# Supply.net
KiCad netlist of a schematic drawn in Altium Designer
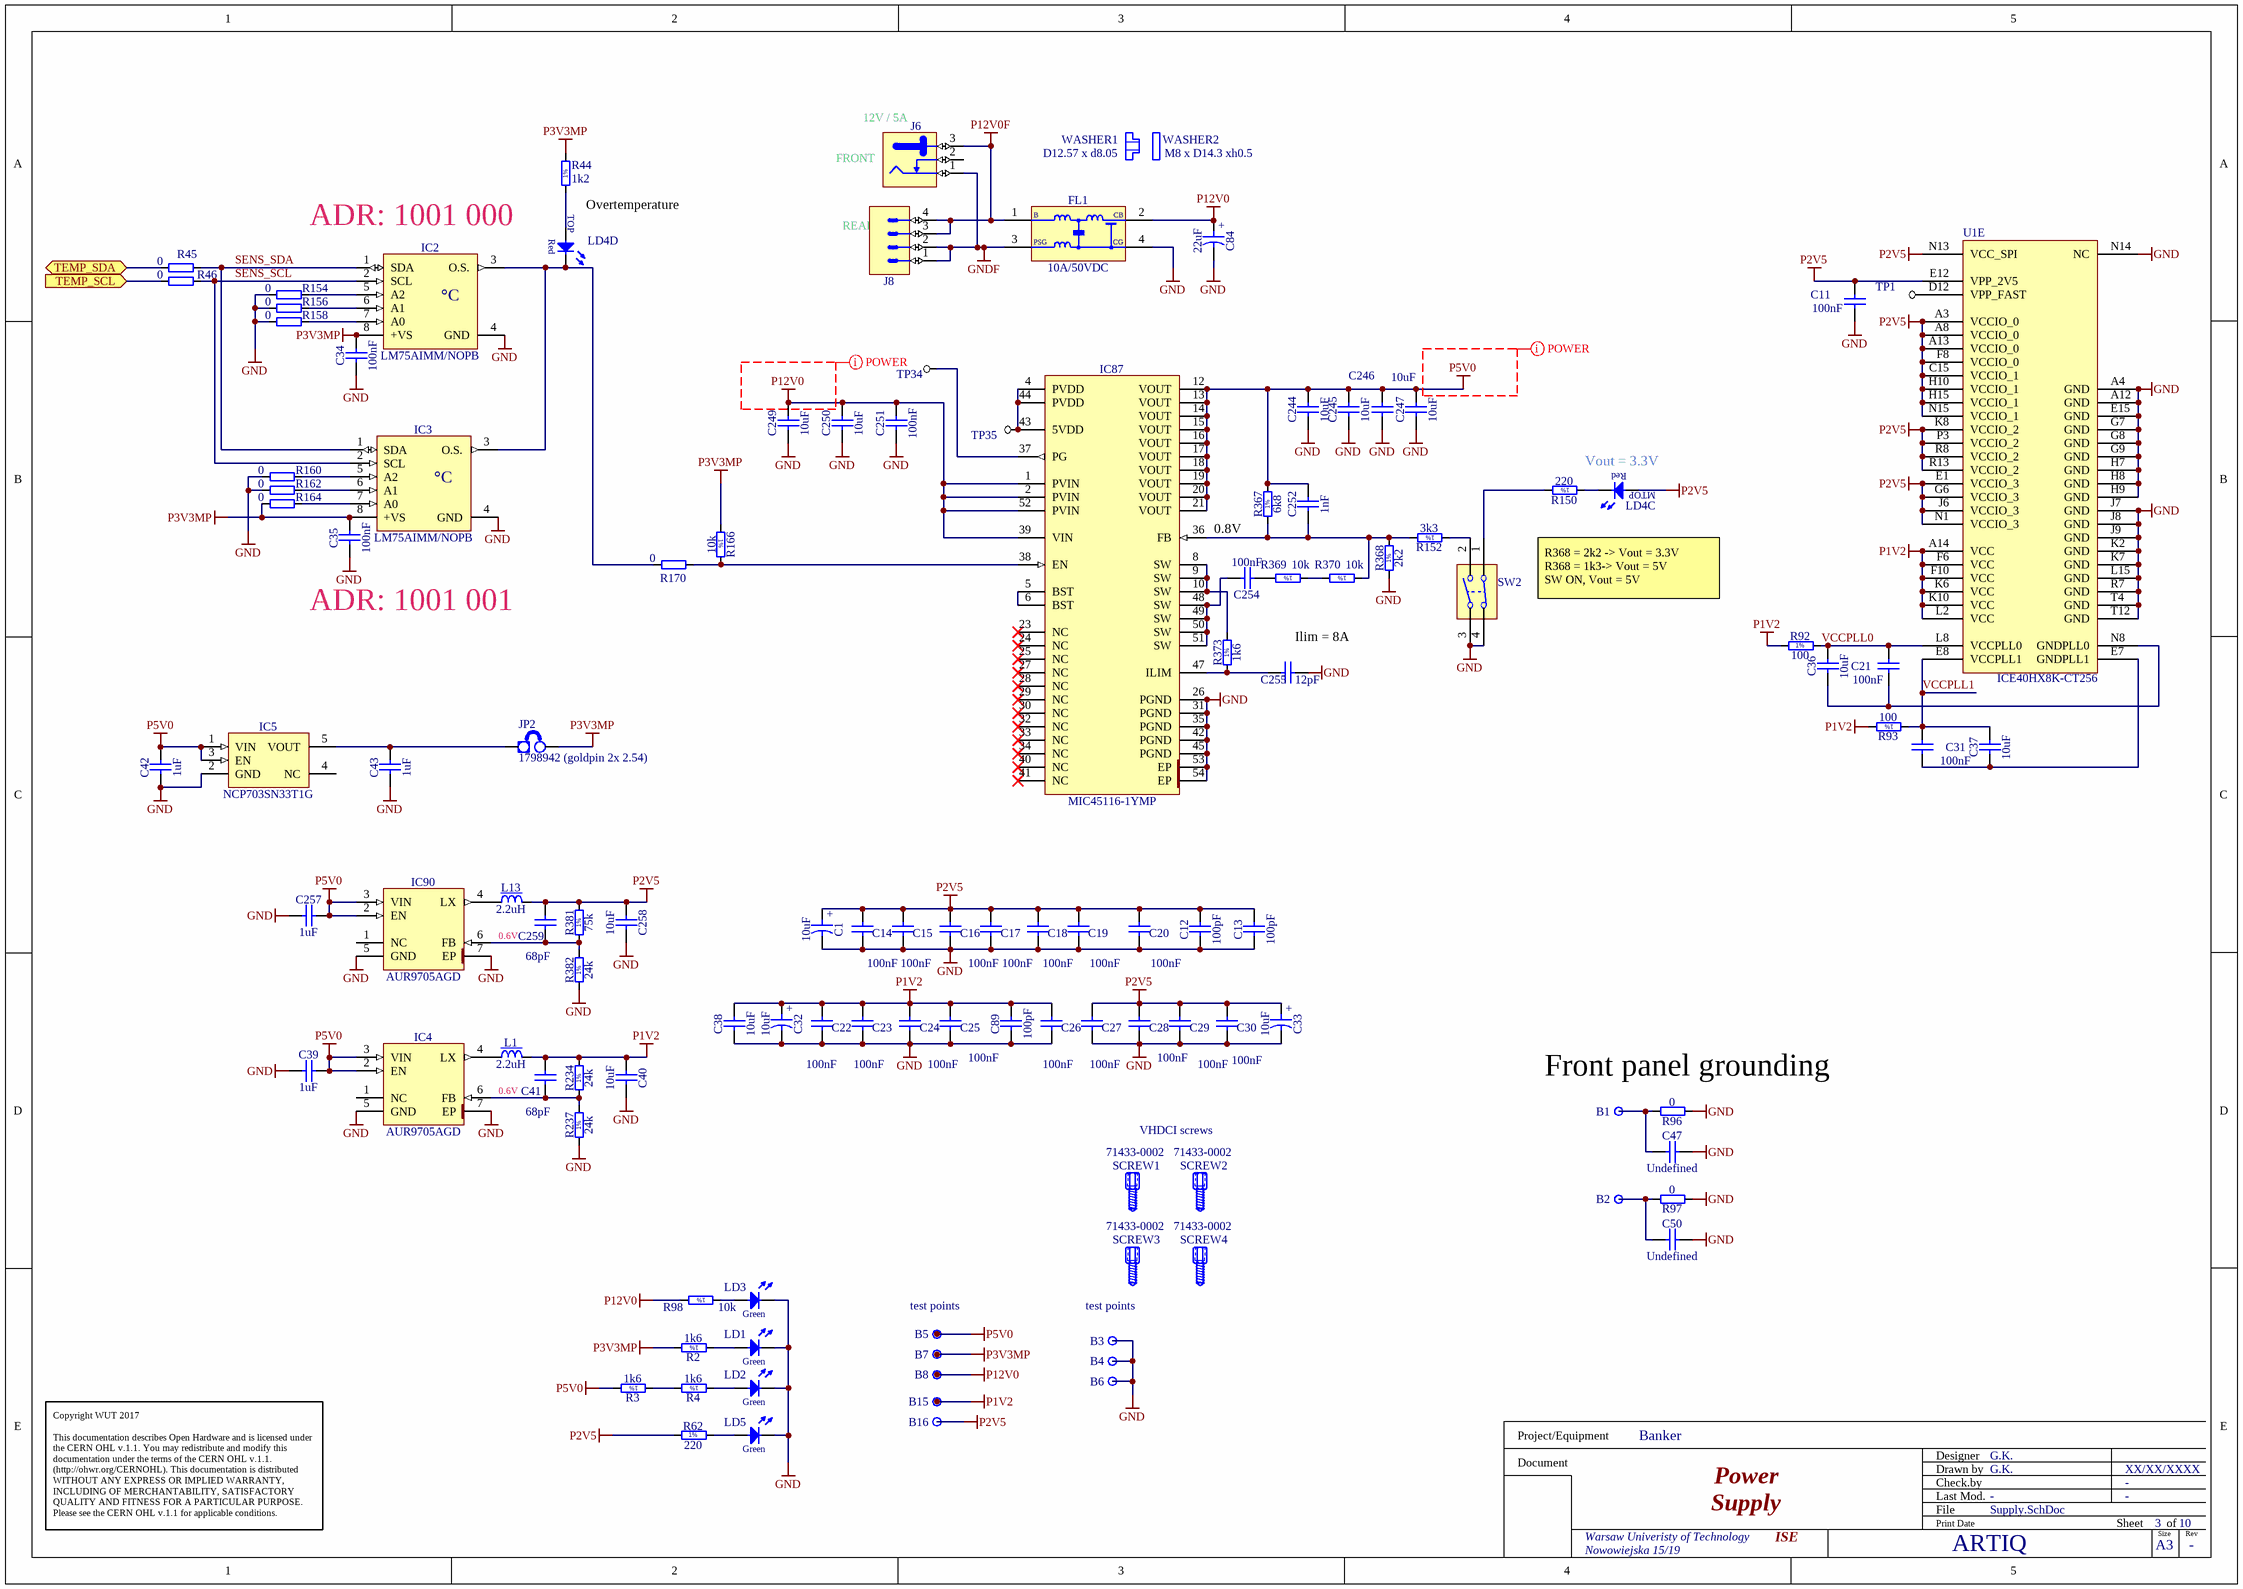
[diagram p0: Supply.SchDoc]

(export (version "E")
  (design (tool "Eeschema 10.0.6"))
  (components
    (comp (ref "B1")
      (value "Plated Hole")
      (footprint "MTG270_500")
      (description "Single Terminal Socket")
      (fields (field (name "PART NUMBER") "PLATED_HOLE2.7_PAD5.0") (field (name "AUTHOR") "CERN DEM JMW"))
      (libsource (lib "Eletro-mechanical") (part "Single Terminal Socket"))
    )
    (comp (ref "B2")
      (value "Plated Hole")
      (footprint "MTG270_500")
      (description "Single Terminal Socket")
      (fields (field (name "PART NUMBER") "PLATED_HOLE2.7_PAD5.0") (field (name "AUTHOR") "CERN DEM JMW"))
      (libsource (lib "Eletro-mechanical") (part "Single Terminal Socket"))
    )
    (comp (ref "B3")
      (value "Plated Hole")
      (footprint "c130h60")
      (description "Single Terminal Socket")
      (fields (field (name "PART NUMBER") "PLATED_HOLE0.6_PAD1.3") (field (name "AUTHOR") "CERN DEM MR"))
      (libsource (lib "Eletro-mechanical") (part "Single Terminal Socket"))
    )
    (comp (ref "B4")
      (value "Plated Hole")
      (footprint "c130h60")
      (description "Single Terminal Socket")
      (fields (field (name "PART NUMBER") "PLATED_HOLE0.6_PAD1.3") (field (name "AUTHOR") "CERN DEM MR"))
      (libsource (lib "Eletro-mechanical") (part "Single Terminal Socket"))
    )
    (comp (ref "B5")
      (value "Plated Hole")
      (footprint "c130h60")
      (description "Single Terminal Socket")
      (fields (field (name "PART NUMBER") "PLATED_HOLE0.6_PAD1.3") (field (name "AUTHOR") "CERN DEM MR"))
      (libsource (lib "Eletro-mechanical") (part "Single Terminal Socket"))
    )
    (comp (ref "B6")
      (value "Plated Hole")
      (footprint "c130h60")
      (description "Single Terminal Socket")
      (fields (field (name "PART NUMBER") "PLATED_HOLE0.6_PAD1.3") (field (name "AUTHOR") "CERN DEM MR"))
      (libsource (lib "Eletro-mechanical") (part "Single Terminal Socket"))
    )
    (comp (ref "B7")
      (value "Plated Hole")
      (footprint "c130h60")
      (description "Single Terminal Socket")
      (fields (field (name "PART NUMBER") "PLATED_HOLE0.6_PAD1.3") (field (name "AUTHOR") "CERN DEM MR"))
      (libsource (lib "Eletro-mechanical") (part "Single Terminal Socket"))
    )
    (comp (ref "B8")
      (value "Plated Hole")
      (footprint "c130h60")
      (description "Single Terminal Socket")
      (fields (field (name "PART NUMBER") "PLATED_HOLE0.6_PAD1.3") (field (name "AUTHOR") "CERN DEM MR"))
      (libsource (lib "Eletro-mechanical") (part "Single Terminal Socket"))
    )
    (comp (ref "B15")
      (value "Plated Hole")
      (footprint "c130h60")
      (description "Single Terminal Socket")
      (fields (field (name "PART NUMBER") "PLATED_HOLE0.6_PAD1.3") (field (name "AUTHOR") "CERN DEM MR"))
      (libsource (lib "Eletro-mechanical") (part "Single Terminal Socket"))
    )
    (comp (ref "B16")
      (value "Plated Hole")
      (footprint "c130h60")
      (description "Single Terminal Socket")
      (fields (field (name "PART NUMBER") "PLATED_HOLE0.6_PAD1.3") (field (name "AUTHOR") "CERN DEM MR"))
      (libsource (lib "Eletro-mechanical") (part "Single Terminal Socket"))
    )
    (comp (ref "C1")
      (value "10uF")
      (footprint "CAPAE430X540N")
      (description "Polarised capacitor")
      (fields
        (field (name "PART NUMBER") "CAE430-540_10UF_16V_20%")
        (field (name "VOLTAGE") "16V")
        (field (name "AUTHOR") "CERN DEM JLC")
      )
      (libsource (lib "Capacitors") (part "Capacitor - polarized"))
    )
    (comp (ref "C11")
      (value "100nF")
      (footprint "CAPC1005X55N")
      (description "Non-polarised capacitor")
      (fields
        (field (name "PART NUMBER") "CC0402_100NF_16V_10%_X5R")
        (field (name "VOLTAGE") "16V")
        (field (name "AUTHOR") "CERN DEM JLC")
      )
      (libsource (lib "Capacitors") (part "Capacitor - non polarized"))
    )
    (comp (ref "C12")
      (value "100pF")
      (footprint "CAPC1608X87N")
      (description "Non-polarised capacitor")
      (fields
        (field (name "PART NUMBER") "CC0603_100PF_50V_10%_X7R")
        (field (name "VOLTAGE") "50V")
        (field (name "AUTHOR") "CERN DEM JLC")
      )
      (libsource (lib "Capacitors") (part "Capacitor - non polarized"))
    )
    (comp (ref "C13")
      (value "100pF")
      (footprint "CAPC1608X87N")
      (description "Non-polarised capacitor")
      (fields
        (field (name "PART NUMBER") "CC0603_100PF_50V_10%_X7R")
        (field (name "VOLTAGE") "50V")
        (field (name "AUTHOR") "CERN DEM JLC")
      )
      (libsource (lib "Capacitors") (part "Capacitor - non polarized"))
    )
    (comp (ref "C14")
      (value "100nF")
      (footprint "CAPC1005X55N")
      (description "Non-polarised capacitor")
      (fields
        (field (name "PART NUMBER") "CC0402_100NF_16V_10%_X5R")
        (field (name "VOLTAGE") "16V")
        (field (name "AUTHOR") "CERN DEM JLC")
      )
      (libsource (lib "Capacitors") (part "Capacitor - non polarized"))
    )
    (comp (ref "C15")
      (value "100nF")
      (footprint "CAPC1005X55N")
      (description "Non-polarised capacitor")
      (fields
        (field (name "PART NUMBER") "CC0402_100NF_16V_10%_X5R")
        (field (name "VOLTAGE") "16V")
        (field (name "AUTHOR") "CERN DEM JLC")
      )
      (libsource (lib "Capacitors") (part "Capacitor - non polarized"))
    )
    (comp (ref "C16")
      (value "100nF")
      (footprint "CAPC1005X55N")
      (description "Non-polarised capacitor")
      (fields
        (field (name "PART NUMBER") "CC0402_100NF_16V_10%_X5R")
        (field (name "VOLTAGE") "16V")
        (field (name "AUTHOR") "CERN DEM JLC")
      )
      (libsource (lib "Capacitors") (part "Capacitor - non polarized"))
    )
    (comp (ref "C17")
      (value "100nF")
      (footprint "CAPC1005X55N")
      (description "Non-polarised capacitor")
      (fields
        (field (name "PART NUMBER") "CC0402_100NF_16V_10%_X5R")
        (field (name "VOLTAGE") "16V")
        (field (name "AUTHOR") "CERN DEM JLC")
      )
      (libsource (lib "Capacitors") (part "Capacitor - non polarized"))
    )
    (comp (ref "C18")
      (value "100nF")
      (footprint "CAPC1005X55N")
      (description "Non-polarised capacitor")
      (fields
        (field (name "PART NUMBER") "CC0402_100NF_16V_10%_X5R")
        (field (name "VOLTAGE") "16V")
        (field (name "AUTHOR") "CERN DEM JLC")
      )
      (libsource (lib "Capacitors") (part "Capacitor - non polarized"))
    )
    (comp (ref "C19")
      (value "100nF")
      (footprint "CAPC1005X55N")
      (description "Non-polarised capacitor")
      (fields
        (field (name "PART NUMBER") "CC0402_100NF_16V_10%_X5R")
        (field (name "VOLTAGE") "16V")
        (field (name "AUTHOR") "CERN DEM JLC")
      )
      (libsource (lib "Capacitors") (part "Capacitor - non polarized"))
    )
    (comp (ref "C20")
      (value "100nF")
      (footprint "CAPC1005X55N")
      (description "Non-polarised capacitor")
      (fields
        (field (name "PART NUMBER") "CC0402_100NF_16V_10%_X5R")
        (field (name "VOLTAGE") "16V")
        (field (name "AUTHOR") "CERN DEM JLC")
      )
      (libsource (lib "Capacitors") (part "Capacitor - non polarized"))
    )
    (comp (ref "C21")
      (value "100nF")
      (footprint "CAPC1005X55N")
      (description "Non-polarised capacitor")
      (fields
        (field (name "PART NUMBER") "CC0402_100NF_16V_10%_X5R")
        (field (name "VOLTAGE") "16V")
        (field (name "AUTHOR") "CERN DEM JLC")
      )
      (libsource (lib "Capacitors") (part "Capacitor - non polarized"))
    )
    (comp (ref "C22")
      (value "100nF")
      (footprint "CAPC1005X55N")
      (description "Non-polarised capacitor")
      (fields
        (field (name "PART NUMBER") "CC0402_100NF_16V_10%_X5R")
        (field (name "VOLTAGE") "16V")
        (field (name "AUTHOR") "CERN DEM JLC")
      )
      (libsource (lib "Capacitors") (part "Capacitor - non polarized"))
    )
    (comp (ref "C23")
      (value "100nF")
      (footprint "CAPC1005X55N")
      (description "Non-polarised capacitor")
      (fields
        (field (name "PART NUMBER") "CC0402_100NF_16V_10%_X5R")
        (field (name "VOLTAGE") "16V")
        (field (name "AUTHOR") "CERN DEM JLC")
      )
      (libsource (lib "Capacitors") (part "Capacitor - non polarized"))
    )
    (comp (ref "C24")
      (value "100nF")
      (footprint "CAPC1005X55N")
      (description "Non-polarised capacitor")
      (fields
        (field (name "PART NUMBER") "CC0402_100NF_16V_10%_X5R")
        (field (name "VOLTAGE") "16V")
        (field (name "AUTHOR") "CERN DEM JLC")
      )
      (libsource (lib "Capacitors") (part "Capacitor - non polarized"))
    )
    (comp (ref "C25")
      (value "100nF")
      (footprint "CAPC1005X55N")
      (description "Non-polarised capacitor")
      (fields
        (field (name "PART NUMBER") "CC0402_100NF_16V_10%_X5R")
        (field (name "VOLTAGE") "16V")
        (field (name "AUTHOR") "CERN DEM JLC")
      )
      (libsource (lib "Capacitors") (part "Capacitor - non polarized"))
    )
    (comp (ref "C26")
      (value "100nF")
      (footprint "CAPC1005X55N")
      (description "Non-polarised capacitor")
      (fields
        (field (name "PART NUMBER") "CC0402_100NF_16V_10%_X5R")
        (field (name "VOLTAGE") "16V")
        (field (name "AUTHOR") "CERN DEM JLC")
      )
      (libsource (lib "Capacitors") (part "Capacitor - non polarized"))
    )
    (comp (ref "C27")
      (value "100nF")
      (footprint "CAPC1005X55N")
      (description "Non-polarised capacitor")
      (fields
        (field (name "PART NUMBER") "CC0402_100NF_16V_10%_X5R")
        (field (name "VOLTAGE") "16V")
        (field (name "AUTHOR") "CERN DEM JLC")
      )
      (libsource (lib "Capacitors") (part "Capacitor - non polarized"))
    )
    (comp (ref "C28")
      (value "100nF")
      (footprint "CAPC1005X55N")
      (description "Non-polarised capacitor")
      (fields
        (field (name "PART NUMBER") "CC0402_100NF_16V_10%_X5R")
        (field (name "VOLTAGE") "16V")
        (field (name "AUTHOR") "CERN DEM JLC")
      )
      (libsource (lib "Capacitors") (part "Capacitor - non polarized"))
    )
    (comp (ref "C29")
      (value "100nF")
      (footprint "CAPC1005X55N")
      (description "Non-polarised capacitor")
      (fields
        (field (name "PART NUMBER") "CC0402_100NF_16V_10%_X5R")
        (field (name "VOLTAGE") "16V")
        (field (name "AUTHOR") "CERN DEM JLC")
      )
      (libsource (lib "Capacitors") (part "Capacitor - non polarized"))
    )
    (comp (ref "C30")
      (value "100nF")
      (footprint "CAPC1005X55N")
      (description "Non-polarised capacitor")
      (fields
        (field (name "PART NUMBER") "CC0402_100NF_16V_10%_X5R")
        (field (name "VOLTAGE") "16V")
        (field (name "AUTHOR") "CERN DEM JLC")
      )
      (libsource (lib "Capacitors") (part "Capacitor - non polarized"))
    )
    (comp (ref "C31")
      (value "100nF")
      (footprint "CAPC1005X55N")
      (description "Non-polarised capacitor")
      (fields
        (field (name "PART NUMBER") "CC0402_100NF_16V_10%_X5R")
        (field (name "VOLTAGE") "16V")
        (field (name "AUTHOR") "CERN DEM JLC")
      )
      (libsource (lib "Capacitors") (part "Capacitor - non polarized"))
    )
    (comp (ref "C32")
      (value "10uF")
      (footprint "CAPAE430X540N")
      (description "Polarised capacitor")
      (fields
        (field (name "PART NUMBER") "CAE430-540_10UF_16V_20%")
        (field (name "VOLTAGE") "16V")
        (field (name "AUTHOR") "CERN DEM JLC")
      )
      (libsource (lib "Capacitors") (part "Capacitor - polarized"))
    )
    (comp (ref "C33")
      (value "10uF")
      (footprint "CAPAE430X540N")
      (description "Polarised capacitor")
      (fields
        (field (name "PART NUMBER") "CAE430-540_10UF_16V_20%")
        (field (name "VOLTAGE") "16V")
        (field (name "AUTHOR") "CERN DEM JLC")
      )
      (libsource (lib "Capacitors") (part "Capacitor - polarized"))
    )
    (comp (ref "C34")
      (value "100nF")
      (footprint "CAPC1005X55N")
      (description "Non-polarised capacitor")
      (fields
        (field (name "PART NUMBER") "CC0402_100NF_16V_10%_X5R")
        (field (name "VOLTAGE") "16V")
        (field (name "AUTHOR") "CERN DEM JLC")
      )
      (libsource (lib "Capacitors") (part "Capacitor - non polarized"))
    )
    (comp (ref "C35")
      (value "100nF")
      (footprint "CAPC1005X55N")
      (description "Non-polarised capacitor")
      (fields
        (field (name "PART NUMBER") "CC0402_100NF_16V_10%_X5R")
        (field (name "VOLTAGE") "16V")
        (field (name "AUTHOR") "CERN DEM JLC")
      )
      (libsource (lib "Capacitors") (part "Capacitor - non polarized"))
    )
    (comp (ref "C36")
      (value "10uF")
      (footprint "CAPC1005X70N")
      (description "Non-polarised capacitor")
      (fields
        (field (name "PART NUMBER") "CC0402_10UF_6.3V_20%_X5R")
        (field (name "VOLTAGE") "6.3V")
        (field (name "AUTHOR") "CERN DEM JLC")
      )
      (libsource (lib "Capacitors") (part "Capacitor - non polarized"))
    )
    (comp (ref "C37")
      (value "10uF")
      (footprint "CAPC1005X70N")
      (description "Non-polarised capacitor")
      (fields
        (field (name "PART NUMBER") "CC0402_10UF_6.3V_20%_X5R")
        (field (name "VOLTAGE") "6.3V")
        (field (name "AUTHOR") "CERN DEM JLC")
      )
      (libsource (lib "Capacitors") (part "Capacitor - non polarized"))
    )
    (comp (ref "C38")
      (value "10uF")
      (footprint "CAPC2012X135N")
      (description "Non-polarised capacitor")
      (fields
        (field (name "PART NUMBER") "CC0805_10UF_16V_10%_X5R")
        (field (name "VOLTAGE") "16V")
        (field (name "AUTHOR") "CERN DEM JLC")
      )
      (libsource (lib "Capacitors") (part "Capacitor - non polarized"))
    )
    (comp (ref "C39")
      (value "1uF")
      (footprint "CAPC1005X55N")
      (description "Non-polarised capacitor")
      (fields
        (field (name "PART NUMBER") "CC0402_1UF_16V_10%_X5R")
        (field (name "VOLTAGE") "16V")
        (field (name "AUTHOR") "CERN DEM JLC")
      )
      (libsource (lib "Capacitors") (part "Capacitor - non polarized"))
    )
    (comp (ref "C40")
      (value "10uF")
      (footprint "CAPC2012X135N")
      (description "Non-polarised capacitor")
      (fields
        (field (name "PART NUMBER") "CC0805_10UF_16V_10%_X5R")
        (field (name "VOLTAGE") "16V")
        (field (name "AUTHOR") "CERN DEM JLC")
      )
      (libsource (lib "Capacitors") (part "Capacitor - non polarized"))
    )
    (comp (ref "C41")
      (value "68pF")
      (footprint "CAPC1608X87N")
      (description "Non-polarised capacitor")
      (fields
        (field (name "PART NUMBER") "CC0603_68PF_50V_5%_NP0")
        (field (name "VOLTAGE") "50V")
        (field (name "AUTHOR") "CERN DEM JLC")
      )
      (libsource (lib "Capacitors") (part "Capacitor - non polarized"))
    )
    (comp (ref "C42")
      (value "1uF")
      (footprint "CAPC2012X140N")
      (description "Non-polarised capacitor")
      (fields
        (field (name "PART NUMBER") "CC0805_1UF_35V_20%_X7R")
        (field (name "VOLTAGE") "35V")
        (field (name "AUTHOR") "CERN DEM JLC")
      )
      (libsource (lib "Capacitors") (part "Capacitor - non polarized"))
    )
    (comp (ref "C43")
      (value "1uF")
      (footprint "CAPC2012X140N")
      (description "Non-polarised capacitor")
      (fields
        (field (name "PART NUMBER") "CC0805_1UF_35V_20%_X7R")
        (field (name "VOLTAGE") "35V")
        (field (name "AUTHOR") "CERN DEM JLC")
      )
      (libsource (lib "Capacitors") (part "Capacitor - non polarized"))
    )
    (comp (ref "C47")
      (value "Undefined")
      (footprint "CAPC2012X135N")
      (description "Non-polarised capacitor")
      (fields (field (name "PART NUMBER") "CC0805_NO-VALUE") (field (name "AUTHOR") "CERN DEM JLC"))
      (libsource (lib "Capacitors") (part "Capacitor - non polarized"))
    )
    (comp (ref "C50")
      (value "Undefined")
      (footprint "CAPC2012X135N")
      (description "Non-polarised capacitor")
      (fields (field (name "PART NUMBER") "CC0805_NO-VALUE") (field (name "AUTHOR") "CERN DEM JLC"))
      (libsource (lib "Capacitors") (part "Capacitor - non polarized"))
    )
    (comp (ref "C84")
      (value "22uF")
      (footprint "CAPAE530X540N")
      (description "Polarised capacitor")
      (fields
        (field (name "PART NUMBER") "CAE530-540_22UF_16V_20%")
        (field (name "VOLTAGE") "16V")
        (field (name "AUTHOR") "CERN DEM JLC")
      )
      (libsource (lib "Capacitors") (part "Capacitor - polarized"))
    )
    (comp (ref "C89")
      (value "100pF")
      (footprint "CAPC1608X87N")
      (description "Non-polarised capacitor")
      (fields
        (field (name "PART NUMBER") "CC0603_100PF_50V_10%_X7R")
        (field (name "VOLTAGE") "50V")
        (field (name "AUTHOR") "CERN DEM JLC")
      )
      (libsource (lib "Capacitors") (part "Capacitor - non polarized"))
    )
    (comp (ref "C244")
      (value "10uF")
      (footprint "CAPC2012X135N")
      (description "Non-polarised capacitor")
      (fields
        (field (name "PART NUMBER") "CC0805_10UF_16V_10%_X5R")
        (field (name "VOLTAGE") "16V")
        (field (name "AUTHOR") "CERN DEM JLC")
      )
      (libsource (lib "Capacitors") (part "Capacitor - non polarized"))
    )
    (comp (ref "C245")
      (value "10uF")
      (footprint "CAPC2012X135N")
      (description "Non-polarised capacitor")
      (fields
        (field (name "PART NUMBER") "CC0805_10UF_16V_10%_X5R")
        (field (name "VOLTAGE") "16V")
        (field (name "AUTHOR") "CERN DEM JLC")
      )
      (libsource (lib "Capacitors") (part "Capacitor - non polarized"))
    )
    (comp (ref "C246")
      (value "10uF")
      (footprint "CAPC2012X135N")
      (description "Non-polarised capacitor")
      (fields
        (field (name "PART NUMBER") "CC0805_10UF_16V_10%_X5R")
        (field (name "VOLTAGE") "16V")
        (field (name "AUTHOR") "CERN DEM JLC")
      )
      (libsource (lib "Capacitors") (part "Capacitor - non polarized"))
    )
    (comp (ref "C247")
      (value "10uF")
      (footprint "CAPC2012X135N")
      (description "Non-polarised capacitor")
      (fields
        (field (name "PART NUMBER") "CC0805_10UF_16V_10%_X5R")
        (field (name "VOLTAGE") "16V")
        (field (name "AUTHOR") "CERN DEM JLC")
      )
      (libsource (lib "Capacitors") (part "Capacitor - non polarized"))
    )
    (comp (ref "C249")
      (value "10uF")
      (footprint "CAPC2012X135N")
      (description "Non-polarised capacitor")
      (fields
        (field (name "PART NUMBER") "CC0805_10UF_16V_10%_X5R")
        (field (name "VOLTAGE") "16V")
        (field (name "AUTHOR") "CERN DEM JLC")
      )
      (libsource (lib "Capacitors") (part "Capacitor - non polarized"))
    )
    (comp (ref "C250")
      (value "10uF")
      (footprint "CAPC2012X135N")
      (description "Non-polarised capacitor")
      (fields
        (field (name "PART NUMBER") "CC0805_10UF_16V_10%_X5R")
        (field (name "VOLTAGE") "16V")
        (field (name "AUTHOR") "CERN DEM JLC")
      )
      (libsource (lib "Capacitors") (part "Capacitor - non polarized"))
    )
    (comp (ref "C251")
      (value "100nF")
      (footprint "CAPC1005X55N")
      (description "Non-polarised capacitor")
      (fields
        (field (name "PART NUMBER") "CC0402_100NF_16V_10%_X5R")
        (field (name "VOLTAGE") "16V")
        (field (name "AUTHOR") "CERN DEM JLC")
      )
      (libsource (lib "Capacitors") (part "Capacitor - non polarized"))
    )
    (comp (ref "C252")
      (value "1nF")
      (footprint "CAPC1608X87N")
      (description "Non-polarised capacitor")
      (fields
        (field (name "PART NUMBER") "CC0603_1NF_100V_10%_X7R")
        (field (name "VOLTAGE") "100V")
        (field (name "AUTHOR") "CERN DEM JLC")
      )
      (libsource (lib "Capacitors") (part "Capacitor - non polarized"))
    )
    (comp (ref "C254")
      (value "100nF")
      (footprint "CAPC1005X55N")
      (description "Non-polarised capacitor")
      (fields
        (field (name "PART NUMBER") "CC0402_100NF_16V_10%_X5R")
        (field (name "VOLTAGE") "16V")
        (field (name "AUTHOR") "CERN DEM JLC")
      )
      (libsource (lib "Capacitors") (part "Capacitor - non polarized"))
    )
    (comp (ref "C255")
      (value "12pF")
      (footprint "CAPC1005X55N")
      (description "Non-polarised capacitor")
      (fields
        (field (name "PART NUMBER") "CC0402_12PF_50V_5%_C0G")
        (field (name "VOLTAGE") "50V")
        (field (name "AUTHOR") "CERN DEM JLC")
      )
      (libsource (lib "Capacitors") (part "Capacitor - non polarized"))
    )
    (comp (ref "C257")
      (value "1uF")
      (footprint "CAPC1005X55N")
      (description "Non-polarised capacitor")
      (fields
        (field (name "PART NUMBER") "CC0402_1UF_16V_10%_X5R")
        (field (name "VOLTAGE") "16V")
        (field (name "AUTHOR") "CERN DEM JLC")
      )
      (libsource (lib "Capacitors") (part "Capacitor - non polarized"))
    )
    (comp (ref "C258")
      (value "10uF")
      (footprint "CAPC2012X135N")
      (description "Non-polarised capacitor")
      (fields
        (field (name "PART NUMBER") "CC0805_10UF_16V_10%_X5R")
        (field (name "VOLTAGE") "16V")
        (field (name "AUTHOR") "CERN DEM JLC")
      )
      (libsource (lib "Capacitors") (part "Capacitor - non polarized"))
    )
    (comp (ref "C259")
      (value "68pF")
      (footprint "CAPC1608X87N")
      (description "Non-polarised capacitor")
      (fields
        (field (name "PART NUMBER") "CC0603_68PF_50V_5%_NP0")
        (field (name "VOLTAGE") "50V")
        (field (name "AUTHOR") "CERN DEM JLC")
      )
      (libsource (lib "Capacitors") (part "Capacitor - non polarized"))
    )
    (comp (ref "FL1")
      (value "10A/50VDC")
      (footprint "FIL_MURATA_BNX02")
      (description "Block Type EMIFIL (LC Combined)")
      (fields
        (field (name "PART NUMBER") "FIL_MURATA_BNX022-01L")
        (field (name "MANUFACTURER") "MURATA")
        (field (name "AUTHOR") "CERN DEM JLC")
      )
      (libsource (lib "Inductors & Transformers") (part "FIL_MURATA_BNX02"))
    )
    (comp (ref "IC2")
      (value "LM75AIMM/NOPB")
      (footprint "SOP65P490X109-8N")
      (description "Digital Temperature Sensor and Thermal Watchdog with Two-Wire Interface")
      (fields (field (name "MANUFACTURER") "TEXAS INSTRUMENTS") (field (name "AUTHOR") "CERN DEM JLC"))
      (libsource (lib "ICs And Semiconductors") (part "LM75"))
    )
    (comp (ref "IC3")
      (value "LM75AIMM/NOPB")
      (footprint "SOP65P490X109-8N")
      (description "Digital Temperature Sensor and Thermal Watchdog with Two-Wire Interface")
      (fields (field (name "MANUFACTURER") "TEXAS INSTRUMENTS") (field (name "AUTHOR") "CERN DEM JLC"))
      (libsource (lib "ICs And Semiconductors") (part "LM75"))
    )
    (comp (ref "IC4")
      (value "AUR9705AGD")
      (footprint "SON65P200X200X80-7N-R65X145")
      (description "0V to 6V Input, 1A, 1.5MHz, Step-Down DC-DC Converter")
      (fields (field (name "MANUFACTURER") "DIODES INCORPORATED") (field (name "AUTHOR") "CERN DEM MR"))
      (libsource (lib "ICs And Semiconductors") (part "AUR9705AGD"))
    )
    (comp (ref "IC5")
      (value "NCP703SN33T1G")
      (footprint "SOT95P275X110-5N")
      (description "3.3V 300mA, Ultra-Low Quiescent Current, IQ 12uA, Ultra-Low Noise, LDO Voltage Regulator")
      (fields (field (name "MANUFACTURER") "ON SEMICONDUCTOR") (field (name "AUTHOR") "CERN DEM JLC"))
      (libsource (lib "ICs And Semiconductors") (part "NCP703SN"))
    )
    (comp (ref "IC87")
      (value "MIC45116-1YMP")
      (footprint "MICROCHIP_H3QFN88-52LD-PL-3")
      (description "0.8V to 85% PVIN (4.75-19V), 6A Synchronous Step-Down Regulator Module")
      (fields (field (name "MANUFACTURER") "MICROCHIP TECHNOLOGY") (field (name "AUTHOR") "CERN DEM JMW"))
      (libsource (lib "ICs And Semiconductors") (part "MIC45116"))
    )
    (comp (ref "IC90")
      (value "AUR9705AGD")
      (footprint "SON65P200X200X80-7N-R65X145")
      (description "0V to 6V Input, 1A, 1.5MHz, Step-Down DC-DC Converter")
      (fields (field (name "MANUFACTURER") "DIODES INCORPORATED") (field (name "AUTHOR") "CERN DEM MR"))
      (libsource (lib "ICs And Semiconductors") (part "AUR9705AGD"))
    )
    (comp (ref "J6")
      (value "Jack")
      (footprint "SWITCHCRAFT_L712RA")
      (description "24V /3. 5A, 2.1mm Diameter Pin, SMD DC Power Supply Connector With  Break Contact")
      (fields
        (field (name "PART NUMBER") "SWITCHCRAFT_L712RA")
        (field (name "MANUFACTURER") "SWITCHCRAFT")
        (field (name "AUTHOR") "GK")
      )
      (libsource (lib "LIBRARY_SCH") (part "CON_DC_5A_THT_RA"))
    )
    (comp (ref "J8")
      (value "Mini-Fit Jr.™")
      (footprint "MOLEX_39-30-0040")
      (description "Connector 4 Male")
      (fields
        (field (name "PART NUMBER") "MOLEX_39-30-0040")
        (field (name "MANUFACTURER") "MOLEX")
        (field (name "AUTHOR") "CERN DEM JLC")
      )
      (libsource (lib "Connectors") (part "Connector 4 Male"))
    )
    (comp (ref "JP2")
      (value "1798942 (goldpin 2x 2.54)")
      (footprint "jump")
      (description "Jumper")
      (libsource (lib "LIBRARY_SCH") (part "JUMPER"))
    )
    (comp (ref "L1")
      (value "2.2uH")
      (footprint "IND_MURATA_LQH44PN_P0")
      (description "Inductor With Core")
      (fields
        (field (name "PART NUMBER") "IND_2.2UH_20%_MURATA_LQH44PN2R2MP0L")
        (field (name "POWER") "1.8A")
        (field (name "AUTHOR") "CERN DEM JLC")
      )
      (libsource (lib "Inductors & Transformers") (part "Inductor With Magnetic core"))
    )
    (comp (ref "L13")
      (value "2.2uH")
      (footprint "IND_MURATA_LQH44PN_P0")
      (description "Inductor With Core")
      (fields
        (field (name "PART NUMBER") "IND_2.2UH_20%_MURATA_LQH44PN2R2MP0L")
        (field (name "POWER") "1.8A")
        (field (name "AUTHOR") "CERN DEM JLC")
      )
      (libsource (lib "Inductors & Transformers") (part "Inductor With Magnetic core"))
    )
    (comp (ref "LD1")
      (value "Green")
      (footprint "LED_KINGBRIGHT_KPH-1608CGCK")
      (description "LED Green 1C 2A")
      (fields
        (field (name "PART NUMBER") "LED_KINGBRIGHT_KPH-1608CGCK")
        (field (name "MANUFACTURER") "KINGBRIGHT")
        (field (name "AUTHOR") "CERN DEM JLC")
      )
      (libsource (lib "ICs And Semiconductors") (part "LED Green 1C 2A"))
    )
    (comp (ref "LD2")
      (value "Green")
      (footprint "LED_KINGBRIGHT_KPH-1608CGCK")
      (description "LED Green 1C 2A")
      (fields
        (field (name "PART NUMBER") "LED_KINGBRIGHT_KPH-1608CGCK")
        (field (name "MANUFACTURER") "KINGBRIGHT")
        (field (name "AUTHOR") "CERN DEM JLC")
      )
      (libsource (lib "ICs And Semiconductors") (part "LED Green 1C 2A"))
    )
    (comp (ref "LD3")
      (value "Green")
      (footprint "LED_KINGBRIGHT_KPH-1608CGCK")
      (description "LED Green 1C 2A")
      (fields
        (field (name "PART NUMBER") "LED_KINGBRIGHT_KPH-1608CGCK")
        (field (name "MANUFACTURER") "KINGBRIGHT")
        (field (name "AUTHOR") "CERN DEM JLC")
      )
      (libsource (lib "ICs And Semiconductors") (part "LED Green 1C 2A"))
    )
    (comp (ref "LD4")
      (value "Green/Green/HeRed/HeRed")
      (footprint "LED_BIVAR_H485CHHGGDL")
      (description "LED x4 G-1C2A-BOT_G-3C4A_H-5C6A_H-7C8A-TOP")
      (fields
        (field (name "PART NUMBER") "LED_BIVAR_H485CHHGGDL")
        (field (name "MANUFACTURER") "BIVAR")
        (field (name "AUTHOR") "CERN DEM BC")
      )
      (libsource (lib "ICs And Semiconductors") (part "LED x4 G-1C2A-BOT_G-3C4A_H-5C6A_H-7C8A-TOP"))
    )
    (comp (ref "LD5")
      (value "Green")
      (footprint "LED_KINGBRIGHT_KPH-1608CGCK")
      (description "LED Green 1C 2A")
      (fields
        (field (name "PART NUMBER") "LED_KINGBRIGHT_KPH-1608CGCK")
        (field (name "MANUFACTURER") "KINGBRIGHT")
        (field (name "AUTHOR") "CERN DEM JLC")
      )
      (libsource (lib "ICs And Semiconductors") (part "LED Green 1C 2A"))
    )
    (comp (ref "R2")
      (value "1k6")
      (footprint "RESC1005X40N")
      (description "Resistor - 1%")
      (fields
        (field (name "PART NUMBER") "R0402_1K6_1%_0.0625W_100PPM")
        (field (name "POWER") "0.0625W")
        (field (name "AUTHOR") "CERN DEM JLC")
      )
      (libsource (lib "Resistors") (part "Resistor - 1%"))
    )
    (comp (ref "R3")
      (value "1k6")
      (footprint "RESC1005X40N")
      (description "Resistor - 1%")
      (fields
        (field (name "PART NUMBER") "R0402_1K6_1%_0.0625W_100PPM")
        (field (name "POWER") "0.0625W")
        (field (name "AUTHOR") "CERN DEM JLC")
      )
      (libsource (lib "Resistors") (part "Resistor - 1%"))
    )
    (comp (ref "R4")
      (value "1k6")
      (footprint "RESC1005X40N")
      (description "Resistor - 1%")
      (fields
        (field (name "PART NUMBER") "R0402_1K6_1%_0.0625W_100PPM")
        (field (name "POWER") "0.0625W")
        (field (name "AUTHOR") "CERN DEM JLC")
      )
      (libsource (lib "Resistors") (part "Resistor - 1%"))
    )
    (comp (ref "R44")
      (value "1k2")
      (footprint "RESC1608X55N")
      (description "Resistor - 1%")
      (fields
        (field (name "PART NUMBER") "R0603_1K2_1%_0.1W_100PPM")
        (field (name "POWER") "0.1W")
        (field (name "AUTHOR") "CERN DEM JLC")
      )
      (libsource (lib "Resistors") (part "Resistor - 1%"))
    )
    (comp (ref "R45")
      (value "0")
      (footprint "RESC1005X40N")
      (description "Resistor")
      (fields
        (field (name "PART NUMBER") "R0402_0R_JUMPER")
        (field (name "MANUFACTURER") "GENERIC")
        (field (name "AUTHOR") "CERN DEM JLC")
      )
      (libsource (lib "Resistors") (part "Resistor"))
    )
    (comp (ref "R46")
      (value "0")
      (footprint "RESC1005X40N")
      (description "Resistor")
      (fields
        (field (name "PART NUMBER") "R0402_0R_JUMPER")
        (field (name "MANUFACTURER") "GENERIC")
        (field (name "AUTHOR") "CERN DEM JLC")
      )
      (libsource (lib "Resistors") (part "Resistor"))
    )
    (comp (ref "R62")
      (value "220")
      (footprint "RESC1608X55N")
      (description "Resistor - 1%")
      (fields
        (field (name "PART NUMBER") "R0603_220R_1%_0.1W_100PPM")
        (field (name "POWER") "0.1W")
        (field (name "AUTHOR") "CERN DEM JLC")
      )
      (libsource (lib "Resistors") (part "Resistor - 1%"))
    )
    (comp (ref "R92")
      (value "100")
      (footprint "RESC1005X40N")
      (description "Resistor - 1%")
      (fields
        (field (name "PART NUMBER") "R0402_100R_1%_0.0625W_100PPM")
        (field (name "POWER") "0.0625W")
        (field (name "AUTHOR") "CERN DEM JLC")
      )
      (libsource (lib "Resistors") (part "Resistor - 1%"))
    )
    (comp (ref "R93")
      (value "100")
      (footprint "RESC1005X40N")
      (description "Resistor - 1%")
      (fields
        (field (name "PART NUMBER") "R0402_100R_1%_0.0625W_100PPM")
        (field (name "POWER") "0.0625W")
        (field (name "AUTHOR") "CERN DEM JLC")
      )
      (libsource (lib "Resistors") (part "Resistor - 1%"))
    )
    (comp (ref "R96")
      (value "0")
      (footprint "RESC1608X55N")
      (description "Resistor")
      (fields
        (field (name "PART NUMBER") "R0603_0R_JUMPER")
        (field (name "MANUFACTURER") "GENERIC")
        (field (name "AUTHOR") "CERN DEM JLC")
      )
      (libsource (lib "Resistors") (part "Resistor"))
    )
    (comp (ref "R97")
      (value "0")
      (footprint "RESC1608X55N")
      (description "Resistor")
      (fields
        (field (name "PART NUMBER") "R0603_0R_JUMPER")
        (field (name "MANUFACTURER") "GENERIC")
        (field (name "AUTHOR") "CERN DEM JLC")
      )
      (libsource (lib "Resistors") (part "Resistor"))
    )
    (comp (ref "R98")
      (value "10k")
      (footprint "RESC1005X40N")
      (description "Resistor - 1%")
      (fields
        (field (name "PART NUMBER") "R0402_10K_1%_0.0625W_100PPM")
        (field (name "POWER") "0.0625W")
        (field (name "AUTHOR") "CERN DEM JLC")
      )
      (libsource (lib "Resistors") (part "Resistor - 1%"))
    )
    (comp (ref "R150")
      (value "220")
      (footprint "RESC1608X55N")
      (description "Resistor - 1%")
      (fields
        (field (name "PART NUMBER") "R0603_220R_1%_0.1W_100PPM")
        (field (name "POWER") "0.1W")
        (field (name "AUTHOR") "CERN DEM JLC")
      )
      (libsource (lib "Resistors") (part "Resistor - 1%"))
    )
    (comp (ref "R152")
      (value "3k3")
      (footprint "RESC1005X40N")
      (description "Resistor - 1%")
      (fields
        (field (name "PART NUMBER") "R0402_3K3_1%_0.0625W_100PPM")
        (field (name "POWER") "0.0625W")
        (field (name "AUTHOR") "CERN DEM JLC")
      )
      (libsource (lib "Resistors") (part "Resistor - 1%"))
    )
    (comp (ref "R154")
      (value "0")
      (footprint "RESC1005X40N")
      (description "Resistor")
      (fields
        (field (name "PART NUMBER") "R0402_0R_JUMPER")
        (field (name "MANUFACTURER") "GENERIC")
        (field (name "AUTHOR") "CERN DEM JLC")
      )
      (libsource (lib "Resistors") (part "Resistor"))
    )
    (comp (ref "R156")
      (value "0")
      (footprint "RESC1005X40N")
      (description "Resistor")
      (fields
        (field (name "PART NUMBER") "R0402_0R_JUMPER")
        (field (name "MANUFACTURER") "GENERIC")
        (field (name "AUTHOR") "CERN DEM JLC")
      )
      (libsource (lib "Resistors") (part "Resistor"))
    )
    (comp (ref "R158")
      (value "0")
      (footprint "RESC1005X40N")
      (description "Resistor")
      (fields
        (field (name "PART NUMBER") "R0402_0R_JUMPER")
        (field (name "MANUFACTURER") "GENERIC")
        (field (name "AUTHOR") "CERN DEM JLC")
      )
      (libsource (lib "Resistors") (part "Resistor"))
    )
    (comp (ref "R160")
      (value "0")
      (footprint "RESC1005X40N")
      (description "Resistor")
      (fields
        (field (name "PART NUMBER") "R0402_0R_JUMPER")
        (field (name "MANUFACTURER") "GENERIC")
        (field (name "AUTHOR") "CERN DEM JLC")
      )
      (libsource (lib "Resistors") (part "Resistor"))
    )
    (comp (ref "R162")
      (value "0")
      (footprint "RESC1005X40N")
      (description "Resistor")
      (fields
        (field (name "PART NUMBER") "R0402_0R_JUMPER")
        (field (name "MANUFACTURER") "GENERIC")
        (field (name "AUTHOR") "CERN DEM JLC")
      )
      (libsource (lib "Resistors") (part "Resistor"))
    )
    (comp (ref "R164")
      (value "0")
      (footprint "RESC1005X40N")
      (description "Resistor")
      (fields
        (field (name "PART NUMBER") "R0402_0R_JUMPER")
        (field (name "MANUFACTURER") "GENERIC")
        (field (name "AUTHOR") "CERN DEM JLC")
      )
      (libsource (lib "Resistors") (part "Resistor"))
    )
    (comp (ref "R166")
      (value "10k")
      (footprint "RESC1005X40N")
      (description "Resistor - 1%")
      (fields
        (field (name "PART NUMBER") "R0402_10K_1%_0.0625W_100PPM")
        (field (name "POWER") "0.0625W")
        (field (name "AUTHOR") "CERN DEM JLC")
      )
      (libsource (lib "Resistors") (part "Resistor - 1%"))
    )
    (comp (ref "R170")
      (value "0")
      (footprint "RESC1005X40N")
      (description "Resistor")
      (fields
        (field (name "PART NUMBER") "R0402_0R_JUMPER")
        (field (name "MANUFACTURER") "GENERIC")
        (field (name "AUTHOR") "CERN DEM JLC")
      )
      (libsource (lib "Resistors") (part "Resistor"))
    )
    (comp (ref "R234")
      (value "24k")
      (footprint "RESC1005X40N")
      (description "Resistor - 1%")
      (fields
        (field (name "PART NUMBER") "R0402_24K_1%_0.0625W_100PPM")
        (field (name "POWER") "0.0625W")
        (field (name "AUTHOR") "CERN DEM JLC")
      )
      (libsource (lib "Resistors") (part "Resistor - 1%"))
    )
    (comp (ref "R237")
      (value "24k")
      (footprint "RESC1005X40N")
      (description "Resistor - 1%")
      (fields
        (field (name "PART NUMBER") "R0402_24K_1%_0.0625W_100PPM")
        (field (name "POWER") "0.0625W")
        (field (name "AUTHOR") "CERN DEM JLC")
      )
      (libsource (lib "Resistors") (part "Resistor - 1%"))
    )
    (comp (ref "R367")
      (value "6k8")
      (footprint "RESC1005X40N")
      (description "Resistor - 1%")
      (fields
        (field (name "PART NUMBER") "R0402_6K8_1%_0.0625W_100PPM")
        (field (name "POWER") "0.0625W")
        (field (name "AUTHOR") "CERN DEM JLC")
      )
      (libsource (lib "Resistors") (part "Resistor - 1%"))
    )
    (comp (ref "R368")
      (value "2k2")
      (footprint "RESC1608X55N")
      (description "Resistor - 1%")
      (fields
        (field (name "PART NUMBER") "R0603_2K2_1%_0.1W_100PPM")
        (field (name "POWER") "0.1W")
        (field (name "AUTHOR") "CERN DEM JLC")
      )
      (libsource (lib "Resistors") (part "Resistor - 1%"))
    )
    (comp (ref "R369")
      (value "10k")
      (footprint "RESC1005X40N")
      (description "Resistor - 1%")
      (fields
        (field (name "PART NUMBER") "R0402_10K_1%_0.0625W_100PPM")
        (field (name "POWER") "0.0625W")
        (field (name "AUTHOR") "CERN DEM JLC")
      )
      (libsource (lib "Resistors") (part "Resistor - 1%"))
    )
    (comp (ref "R370")
      (value "10k")
      (footprint "RESC1005X40N")
      (description "Resistor - 1%")
      (fields
        (field (name "PART NUMBER") "R0402_10K_1%_0.0625W_100PPM")
        (field (name "POWER") "0.0625W")
        (field (name "AUTHOR") "CERN DEM JLC")
      )
      (libsource (lib "Resistors") (part "Resistor - 1%"))
    )
    (comp (ref "R373")
      (value "1k6")
      (footprint "RESC1005X40N")
      (description "Resistor - 1%")
      (fields
        (field (name "PART NUMBER") "R0402_1K6_1%_0.0625W_100PPM")
        (field (name "POWER") "0.0625W")
        (field (name "AUTHOR") "CERN DEM JLC")
      )
      (libsource (lib "Resistors") (part "Resistor - 1%"))
    )
    (comp (ref "R381")
      (value "75k")
      (footprint "RESC1005X40N")
      (description "Resistor - 1%")
      (fields
        (field (name "PART NUMBER") "R0402_75K_1%_0.0625W_100PPM")
        (field (name "POWER") "0.0625W")
        (field (name "AUTHOR") "CERN DEM JLC")
      )
      (libsource (lib "Resistors") (part "Resistor - 1%"))
    )
    (comp (ref "R382")
      (value "24k")
      (footprint "RESC1005X40N")
      (description "Resistor - 1%")
      (fields
        (field (name "PART NUMBER") "R0402_24K_1%_0.0625W_100PPM")
        (field (name "POWER") "0.0625W")
        (field (name "AUTHOR") "CERN DEM JLC")
      )
      (libsource (lib "Resistors") (part "Resistor - 1%"))
    )
    (comp (ref "SCREW1")
      (value "71433-0002")
      (footprint "MOLEX_71433-0002")
      (description "VHDCI Female Screw Lock")
      (fields
        (field (name "PART NUMBER") "MOLEX_71433-0002")
        (field (name "MANUFACTURER") "Molex")
        (field (name "AUTHOR") "GK")
      )
      (libsource (lib "LIBRARY_SCH") (part "MECH_VHDCI_screw_lock"))
    )
    (comp (ref "SCREW2")
      (value "71433-0002")
      (footprint "MOLEX_71433-0002")
      (description "VHDCI Female Screw Lock")
      (fields
        (field (name "PART NUMBER") "MOLEX_71433-0002")
        (field (name "MANUFACTURER") "Molex")
        (field (name "AUTHOR") "GK")
      )
      (libsource (lib "LIBRARY_SCH") (part "MECH_VHDCI_screw_lock"))
    )
    (comp (ref "SCREW3")
      (value "71433-0002")
      (footprint "MOLEX_71433-0002")
      (description "VHDCI Female Screw Lock")
      (fields
        (field (name "PART NUMBER") "MOLEX_71433-0002")
        (field (name "MANUFACTURER") "Molex")
        (field (name "AUTHOR") "GK")
      )
      (libsource (lib "LIBRARY_SCH") (part "MECH_VHDCI_screw_lock"))
    )
    (comp (ref "SCREW4")
      (value "71433-0002")
      (footprint "MOLEX_71433-0002")
      (description "VHDCI Female Screw Lock")
      (fields
        (field (name "PART NUMBER") "MOLEX_71433-0002")
        (field (name "MANUFACTURER") "Molex")
        (field (name "AUTHOR") "GK")
      )
      (libsource (lib "LIBRARY_SCH") (part "MECH_VHDCI_screw_lock"))
    )
    (comp (ref "SW2")
      (value "Switch")
      (footprint "SW_CTS_204-121ST")
      (description "2x SPST DIP Switch 1NO + 1NF")
      (fields
        (field (name "PART NUMBER") "SW_CTS_204-121ST")
        (field (name "MANUFACTURER") "CTS")
        (field (name "AUTHOR") "CERN DEM JLC")
      )
      (libsource (lib "Eletro-mechanical") (part "SW_CTS_204-121ST"))
    )
    (comp (ref "TP1")
      (value "TP")
      (footprint "TP")
      (description "Testpoint")
      (libsource (lib "LIBRARY_SCH") (part "TP"))
    )
    (comp (ref "TP34")
      (value "TP")
      (footprint "TP")
      (description "Testpoint")
      (libsource (lib "LIBRARY_SCH") (part "TP"))
    )
    (comp (ref "TP35")
      (value "TP")
      (footprint "TP")
      (description "Testpoint")
      (libsource (lib "LIBRARY_SCH") (part "TP"))
    )
    (comp (ref "U1")
      (value "ICE40HX8K-CT256")
      (footprint "LATC-caBGA-256")
      (fields (field (name "MANUFACTURER") "Lattice Semiconductor"))
      (libsource (lib "Altium Content Vault") (part "LATC-HX8K-caBGA-256"))
    )
    (comp (ref "WASHER1")
      (value "D12.57 x d8.05")
      (footprint "Washer_s4263")
      (description "8mm_Shoulder Washer")
      (fields
        (field (name "PART NUMBER") "Switchcraft_s4263")
        (field (name "MANUFACTURER") "Switchcraft")
        (field (name "AUTHOR") "GK")
      )
      (libsource (lib "LIBRARY_SCH") (part "MECH_Washer_s4263"))
    )
    (comp (ref "WASHER2")
      (value "M8 x D14.3 xh0.5")
      (footprint "Washer_M8x0.5x14.3")
      (description "M8 x0.5x14.3 Nylon Washer")
      (fields
        (field (name "PART NUMBER") "WS-M 8-0.5(14.3)")
        (field (name "MANUFACTURER") "ADSYS ELEMENTY")
        (field (name "AUTHOR") "GK")
      )
      (libsource (lib "LIBRARY_SCH") (part "MECH_Washer_M8x0.5x14.3"))
    )
  )
  (nets
    (net (code "1") (name "/SENS_SCL") (class "Default")
      (node (ref "IC2") (pin "2") (pinfunction "SCL_2") (pintype "input"))
      (node (ref "IC3") (pin "2") (pinfunction "SCL_2") (pintype "input"))
      (node (ref "R46") (pin "2") (pinfunction "2_2") (pintype "passive"))
    )
    (net (code "2") (name "/SENS_SDA") (class "Default")
      (node (ref "IC2") (pin "1") (pinfunction "SDA_1") (pintype "bidirectional"))
      (node (ref "IC3") (pin "1") (pinfunction "SDA_1") (pintype "bidirectional"))
      (node (ref "R45") (pin "2") (pinfunction "2_2") (pintype "passive"))
    )
    (net (code "3") (name "/TEMP_SCL") (class "Default")
      (node (ref "R46") (pin "1") (pinfunction "1_1") (pintype "passive"))
    )
    (net (code "4") (name "/TEMP_SDA") (class "Default")
      (node (ref "R45") (pin "1") (pinfunction "1_1") (pintype "passive"))
    )
    (net (code "5") (name "/VCCPLL0") (class "Default")
      (node (ref "C21") (pin "2") (pinfunction "2_2") (pintype "passive"))
      (node (ref "C36") (pin "2") (pinfunction "2_2") (pintype "passive"))
      (node (ref "R92") (pin "2") (pinfunction "2_2") (pintype "passive"))
      (node (ref "U1") (pin "L8") (pinfunction "VCCPLL0_L8") (pintype "power_in"))
    )
    (net (code "6") (name "/VCCPLL1") (class "Default")
      (node (ref "C31") (pin "2") (pinfunction "2_2") (pintype "passive"))
      (node (ref "C37") (pin "2") (pinfunction "2_2") (pintype "passive"))
      (node (ref "R93") (pin "1") (pinfunction "1_1") (pintype "passive"))
      (node (ref "U1") (pin "E8") (pinfunction "VCCPLL1_E8") (pintype "power_in"))
    )
    (net (code "7") (name "GND") (class "Default")
      (node (ref "B3") (pin "1") (pinfunction "1_1") (pintype "bidirectional"))
      (node (ref "B4") (pin "1") (pinfunction "1_1") (pintype "bidirectional"))
      (node (ref "B6") (pin "1") (pinfunction "1_1") (pintype "bidirectional"))
      (node (ref "C1") (pin "2") (pinfunction "2_2") (pintype "passive"))
      (node (ref "C11") (pin "1") (pinfunction "1_1") (pintype "passive"))
      (node (ref "C12") (pin "1") (pinfunction "1_1") (pintype "passive"))
      (node (ref "C13") (pin "1") (pinfunction "1_1") (pintype "passive"))
      (node (ref "C14") (pin "1") (pinfunction "1_1") (pintype "passive"))
      (node (ref "C15") (pin "1") (pinfunction "1_1") (pintype "passive"))
      (node (ref "C16") (pin "1") (pinfunction "1_1") (pintype "passive"))
      (node (ref "C17") (pin "1") (pinfunction "1_1") (pintype "passive"))
      (node (ref "C18") (pin "1") (pinfunction "1_1") (pintype "passive"))
      (node (ref "C19") (pin "1") (pinfunction "1_1") (pintype "passive"))
      (node (ref "C20") (pin "1") (pinfunction "1_1") (pintype "passive"))
      (node (ref "C22") (pin "1") (pinfunction "1_1") (pintype "passive"))
      (node (ref "C23") (pin "1") (pinfunction "1_1") (pintype "passive"))
      (node (ref "C24") (pin "1") (pinfunction "1_1") (pintype "passive"))
      (node (ref "C244") (pin "1") (pinfunction "1_1") (pintype "passive"))
      (node (ref "C245") (pin "1") (pinfunction "1_1") (pintype "passive"))
      (node (ref "C246") (pin "1") (pinfunction "1_1") (pintype "passive"))
      (node (ref "C247") (pin "1") (pinfunction "1_1") (pintype "passive"))
      (node (ref "C249") (pin "1") (pinfunction "1_1") (pintype "passive"))
      (node (ref "C25") (pin "1") (pinfunction "1_1") (pintype "passive"))
      (node (ref "C250") (pin "1") (pinfunction "1_1") (pintype "passive"))
      (node (ref "C251") (pin "1") (pinfunction "1_1") (pintype "passive"))
      (node (ref "C255") (pin "1") (pinfunction "1_1") (pintype "passive"))
      (node (ref "C257") (pin "1") (pinfunction "1_1") (pintype "passive"))
      (node (ref "C258") (pin "2") (pinfunction "2_2") (pintype "passive"))
      (node (ref "C26") (pin "1") (pinfunction "1_1") (pintype "passive"))
      (node (ref "C27") (pin "1") (pinfunction "1_1") (pintype "passive"))
      (node (ref "C28") (pin "1") (pinfunction "1_1") (pintype "passive"))
      (node (ref "C29") (pin "1") (pinfunction "1_1") (pintype "passive"))
      (node (ref "C30") (pin "1") (pinfunction "1_1") (pintype "passive"))
      (node (ref "C32") (pin "2") (pinfunction "2_2") (pintype "passive"))
      (node (ref "C33") (pin "2") (pinfunction "2_2") (pintype "passive"))
      (node (ref "C34") (pin "1") (pinfunction "1_1") (pintype "passive"))
      (node (ref "C35") (pin "1") (pinfunction "1_1") (pintype "passive"))
      (node (ref "C38") (pin "1") (pinfunction "1_1") (pintype "passive"))
      (node (ref "C39") (pin "1") (pinfunction "1_1") (pintype "passive"))
      (node (ref "C40") (pin "2") (pinfunction "2_2") (pintype "passive"))
      (node (ref "C42") (pin "1") (pinfunction "1_1") (pintype "passive"))
      (node (ref "C43") (pin "1") (pinfunction "1_1") (pintype "passive"))
      (node (ref "C47") (pin "2") (pinfunction "2_2") (pintype "passive"))
      (node (ref "C50") (pin "2") (pinfunction "2_2") (pintype "passive"))
      (node (ref "C84") (pin "2") (pinfunction "2_2") (pintype "passive"))
      (node (ref "C89") (pin "1") (pinfunction "1_1") (pintype "passive"))
      (node (ref "FL1") (pin "4") (pinfunction "CG_4") (pintype "passive"))
      (node (ref "IC2") (pin "4") (pinfunction "GND_4") (pintype "power_in"))
      (node (ref "IC3") (pin "4") (pinfunction "GND_4") (pintype "power_in"))
      (node (ref "IC4") (pin "5") (pinfunction "GND_5") (pintype "power_in"))
      (node (ref "IC4") (pin "7") (pinfunction "EP_7") (pintype "passive"))
      (node (ref "IC5") (pin "2") (pinfunction "GND_2") (pintype "power_in"))
      (node (ref "IC87") (pin "26") (pinfunction "PGND_26") (pintype "power_in"))
      (node (ref "IC87") (pin "31") (pinfunction "PGND_31") (pintype "power_in"))
      (node (ref "IC87") (pin "35") (pinfunction "PGND_35") (pintype "power_in"))
      (node (ref "IC87") (pin "42") (pinfunction "PGND_42") (pintype "power_in"))
      (node (ref "IC87") (pin "45") (pinfunction "PGND_45") (pintype "power_in"))
      (node (ref "IC87") (pin "53") (pinfunction "EP_53") (pintype "power_in"))
      (node (ref "IC87") (pin "54") (pinfunction "EP_54") (pintype "power_in"))
      (node (ref "IC90") (pin "5") (pinfunction "GND_5") (pintype "power_in"))
      (node (ref "IC90") (pin "7") (pinfunction "EP_7") (pintype "passive"))
      (node (ref "LD1") (pin "1") (pinfunction "C_1") (pintype "passive"))
      (node (ref "LD2") (pin "1") (pinfunction "C_1") (pintype "passive"))
      (node (ref "LD3") (pin "1") (pinfunction "C_1") (pintype "passive"))
      (node (ref "LD5") (pin "1") (pinfunction "C_1") (pintype "passive"))
      (node (ref "R154") (pin "1") (pinfunction "1_1") (pintype "passive"))
      (node (ref "R156") (pin "1") (pinfunction "1_1") (pintype "passive"))
      (node (ref "R158") (pin "1") (pinfunction "1_1") (pintype "passive"))
      (node (ref "R160") (pin "1") (pinfunction "1_1") (pintype "passive"))
      (node (ref "R162") (pin "1") (pinfunction "1_1") (pintype "passive"))
      (node (ref "R237") (pin "1") (pinfunction "1_1") (pintype "passive"))
      (node (ref "R368") (pin "1") (pinfunction "1_1") (pintype "passive"))
      (node (ref "R382") (pin "1") (pinfunction "1_1") (pintype "passive"))
      (node (ref "R96") (pin "1") (pinfunction "1_1") (pintype "passive"))
      (node (ref "R97") (pin "1") (pinfunction "1_1") (pintype "passive"))
      (node (ref "SW2") (pin "3") (pinfunction "3_3") (pintype "passive"))
      (node (ref "SW2") (pin "4") (pinfunction "4_4") (pintype "passive"))
      (node (ref "U1") (pin "A12") (pinfunction "GND_A12") (pintype "power_in"))
      (node (ref "U1") (pin "A4") (pinfunction "GND_A4") (pintype "power_in"))
      (node (ref "U1") (pin "E15") (pinfunction "GND_E15") (pintype "power_in"))
      (node (ref "U1") (pin "G7") (pinfunction "GND_G7") (pintype "power_in"))
      (node (ref "U1") (pin "G8") (pinfunction "GND_G8") (pintype "power_in"))
      (node (ref "U1") (pin "G9") (pinfunction "GND_G9") (pintype "power_in"))
      (node (ref "U1") (pin "H7") (pinfunction "GND_H7") (pintype "power_in"))
      (node (ref "U1") (pin "H8") (pinfunction "GND_H8") (pintype "power_in"))
      (node (ref "U1") (pin "H9") (pinfunction "GND_H9") (pintype "power_in"))
      (node (ref "U1") (pin "J7") (pinfunction "GND_J7") (pintype "power_in"))
      (node (ref "U1") (pin "J8") (pinfunction "GND_J8") (pintype "power_in"))
      (node (ref "U1") (pin "J9") (pinfunction "GND_J9") (pintype "power_in"))
      (node (ref "U1") (pin "K2") (pinfunction "GND_K2") (pintype "power_in"))
      (node (ref "U1") (pin "K7") (pinfunction "GND_K7") (pintype "power_in"))
      (node (ref "U1") (pin "L15") (pinfunction "GND_L15") (pintype "power_in"))
      (node (ref "U1") (pin "N14") (pinfunction "NC_N14") (pintype "passive"))
      (node (ref "U1") (pin "R7") (pinfunction "GND_R7") (pintype "power_in"))
      (node (ref "U1") (pin "T12") (pinfunction "GND_T12") (pintype "power_in"))
      (node (ref "U1") (pin "T4") (pinfunction "GND_T4") (pintype "power_in"))
    )
    (net (code "8") (name "GNDF") (class "Default")
      (node (ref "FL1") (pin "3") (pinfunction "PSG_3") (pintype "passive"))
      (node (ref "J6") (pin "1") (pinfunction "1_1") (pintype "bidirectional"))
      (node (ref "J8") (pin "1") (pinfunction "1_1") (pintype "bidirectional"))
      (node (ref "J8") (pin "2") (pinfunction "2_2") (pintype "bidirectional"))
    )
    (net (code "9") (name "Net-(B1-Pad1)") (class "Default")
      (node (ref "B1") (pin "1") (pinfunction "1_1") (pintype "bidirectional"))
      (node (ref "C47") (pin "1") (pinfunction "1_1") (pintype "passive"))
      (node (ref "R96") (pin "2") (pinfunction "2_2") (pintype "passive"))
    )
    (net (code "10") (name "Net-(B2-Pad1)") (class "Default")
      (node (ref "B2") (pin "1") (pinfunction "1_1") (pintype "bidirectional"))
      (node (ref "C50") (pin "1") (pinfunction "1_1") (pintype "passive"))
      (node (ref "R97") (pin "2") (pinfunction "2_2") (pintype "passive"))
    )
    (net (code "11") (name "Net-(C254-Pad1)") (class "Default")
      (node (ref "C254") (pin "1") (pinfunction "1_1") (pintype "passive"))
      (node (ref "R369") (pin "2") (pinfunction "2_2") (pintype "passive"))
    )
    (net (code "12") (name "Net-(C254-Pad2)") (class "Default")
      (node (ref "C254") (pin "2") (pinfunction "2_2") (pintype "passive"))
      (node (ref "IC87") (pin "48") (pinfunction "SW_48") (pintype "passive"))
      (node (ref "IC87") (pin "49") (pinfunction "SW_49") (pintype "passive"))
      (node (ref "IC87") (pin "50") (pinfunction "SW_50") (pintype "passive"))
      (node (ref "IC87") (pin "51") (pinfunction "SW_51") (pintype "passive"))
    )
    (net (code "13") (name "Net-(IC2-A0)") (class "Default")
      (node (ref "IC2") (pin "7") (pinfunction "A0_7") (pintype "input"))
      (node (ref "R158") (pin "2") (pinfunction "2_2") (pintype "passive"))
    )
    (net (code "14") (name "Net-(IC2-A1)") (class "Default")
      (node (ref "IC2") (pin "6") (pinfunction "A1_6") (pintype "input"))
      (node (ref "R156") (pin "2") (pinfunction "2_2") (pintype "passive"))
    )
    (net (code "15") (name "Net-(IC2-A2)") (class "Default")
      (node (ref "IC2") (pin "5") (pinfunction "A2_5") (pintype "input"))
      (node (ref "R154") (pin "2") (pinfunction "2_2") (pintype "passive"))
    )
    (net (code "16") (name "Net-(IC2-O.S.)") (class "Default")
      (node (ref "IC2") (pin "3") (pinfunction "O.S._3") (pintype "output"))
      (node (ref "IC3") (pin "3") (pinfunction "O.S._3") (pintype "output"))
      (node (ref "LD4") (pin "7") (pinfunction "C_7") (pintype "passive"))
      (node (ref "R170") (pin "1") (pinfunction "1_1") (pintype "passive"))
    )
    (net (code "17") (name "Net-(IC3-A0)") (class "Default")
      (node (ref "IC3") (pin "7") (pinfunction "A0_7") (pintype "input"))
      (node (ref "R164") (pin "2") (pinfunction "2_2") (pintype "passive"))
    )
    (net (code "18") (name "Net-(IC3-A1)") (class "Default")
      (node (ref "IC3") (pin "6") (pinfunction "A1_6") (pintype "input"))
      (node (ref "R162") (pin "2") (pinfunction "2_2") (pintype "passive"))
    )
    (net (code "19") (name "Net-(IC3-A2)") (class "Default")
      (node (ref "IC3") (pin "5") (pinfunction "A2_5") (pintype "input"))
      (node (ref "R160") (pin "2") (pinfunction "2_2") (pintype "passive"))
    )
    (net (code "20") (name "Net-(IC4-FB)") (class "Default")
      (node (ref "C41") (pin "1") (pinfunction "1_1") (pintype "passive"))
      (node (ref "IC4") (pin "6") (pinfunction "FB_6") (pintype "input"))
      (node (ref "R234") (pin "1") (pinfunction "1_1") (pintype "passive"))
      (node (ref "R237") (pin "2") (pinfunction "2_2") (pintype "passive"))
    )
    (net (code "21") (name "Net-(IC4-LX)") (class "Default")
      (node (ref "IC4") (pin "4") (pinfunction "LX_4") (pintype "output"))
      (node (ref "L1") (pin "1") (pinfunction "1_1") (pintype "passive"))
    )
    (net (code "22") (name "Net-(IC5-VOUT)") (class "Default")
      (node (ref "C43") (pin "2") (pinfunction "2_2") (pintype "passive"))
      (node (ref "IC5") (pin "5") (pinfunction "VOUT_5") (pintype "power_in"))
      (node (ref "JP2") (pin "1") (pinfunction "E1_1") (pintype "passive"))
    )
    (net (code "23") (name "Net-(IC87-5VDD)") (class "Default")
      (node (ref "IC87") (pin "4") (pinfunction "PVDD_4") (pintype "power_in"))
      (node (ref "IC87") (pin "43") (pinfunction "5VDD_43") (pintype "power_in"))
      (node (ref "IC87") (pin "44") (pinfunction "PVDD_44") (pintype "power_in"))
      (node (ref "TP35") (pin "1") (pintype "passive"))
    )
    (net (code "24") (name "Net-(IC87-BST-Pad5)") (class "Default")
      (node (ref "IC87") (pin "5") (pinfunction "BST_5") (pintype "passive"))
      (node (ref "IC87") (pin "6") (pinfunction "BST_6") (pintype "passive"))
    )
    (net (code "25") (name "Net-(IC87-EN)") (class "Default")
      (node (ref "IC87") (pin "38") (pinfunction "EN_38") (pintype "input"))
      (node (ref "R166") (pin "2") (pinfunction "2_2") (pintype "passive"))
      (node (ref "R170") (pin "2") (pinfunction "2_2") (pintype "passive"))
    )
    (net (code "26") (name "Net-(IC87-FB)") (class "Default")
      (node (ref "C252") (pin "1") (pinfunction "1_1") (pintype "passive"))
      (node (ref "IC87") (pin "36") (pinfunction "FB_36") (pintype "input"))
      (node (ref "R152") (pin "2") (pinfunction "2_2") (pintype "passive"))
      (node (ref "R367") (pin "1") (pinfunction "1_1") (pintype "passive"))
      (node (ref "R368") (pin "2") (pinfunction "2_2") (pintype "passive"))
      (node (ref "R370") (pin "1") (pinfunction "1_1") (pintype "passive"))
    )
    (net (code "27") (name "Net-(IC87-ILIM)") (class "Default")
      (node (ref "C255") (pin "2") (pinfunction "2_2") (pintype "passive"))
      (node (ref "IC87") (pin "47") (pinfunction "ILIM_47") (pintype "passive"))
      (node (ref "R373") (pin "1") (pinfunction "1_1") (pintype "passive"))
    )
    (net (code "28") (name "Net-(IC87-PG)") (class "Default")
      (node (ref "IC87") (pin "37") (pinfunction "PG_37") (pintype "output"))
      (node (ref "TP34") (pin "1") (pintype "passive"))
    )
    (net (code "29") (name "Net-(IC87-SW-Pad10)") (class "Default")
      (node (ref "IC87") (pin "10") (pinfunction "SW_10") (pintype "passive"))
      (node (ref "IC87") (pin "8") (pinfunction "SW_8") (pintype "passive"))
      (node (ref "IC87") (pin "9") (pinfunction "SW_9") (pintype "passive"))
      (node (ref "R373") (pin "2") (pinfunction "2_2") (pintype "passive"))
    )
    (net (code "30") (name "Net-(IC90-FB)") (class "Default")
      (node (ref "C259") (pin "1") (pinfunction "1_1") (pintype "passive"))
      (node (ref "IC90") (pin "6") (pinfunction "FB_6") (pintype "input"))
      (node (ref "R381") (pin "1") (pinfunction "1_1") (pintype "passive"))
      (node (ref "R382") (pin "2") (pinfunction "2_2") (pintype "passive"))
    )
    (net (code "31") (name "Net-(IC90-LX)") (class "Default")
      (node (ref "IC90") (pin "4") (pinfunction "LX_4") (pintype "output"))
      (node (ref "L13") (pin "1") (pinfunction "1_1") (pintype "passive"))
    )
    (net (code "32") (name "Net-(LD1-A)") (class "Default")
      (node (ref "LD1") (pin "2") (pinfunction "A_2") (pintype "passive"))
      (node (ref "R2") (pin "1") (pinfunction "1_1") (pintype "passive"))
    )
    (net (code "33") (name "Net-(LD2-A)") (class "Default")
      (node (ref "LD2") (pin "2") (pinfunction "A_2") (pintype "passive"))
      (node (ref "R4") (pin "1") (pinfunction "1_1") (pintype "passive"))
    )
    (net (code "34") (name "Net-(LD3-A)") (class "Default")
      (node (ref "LD3") (pin "2") (pinfunction "A_2") (pintype "passive"))
      (node (ref "R98") (pin "1") (pinfunction "1_1") (pintype "passive"))
    )
    (net (code "35") (name "Net-(LD4C-C)") (class "Default")
      (node (ref "LD4") (pin "5") (pinfunction "C_5") (pintype "passive"))
      (node (ref "R150") (pin "1") (pinfunction "1_1") (pintype "passive"))
    )
    (net (code "36") (name "Net-(LD4D-A)") (class "Default")
      (node (ref "LD4") (pin "8") (pinfunction "A_8") (pintype "passive"))
      (node (ref "R44") (pin "1") (pinfunction "1_1") (pintype "passive"))
    )
    (net (code "37") (name "Net-(LD5-A)") (class "Default")
      (node (ref "LD5") (pin "2") (pinfunction "A_2") (pintype "passive"))
      (node (ref "R62") (pin "2") (pinfunction "2_2") (pintype "passive"))
    )
    (net (code "38") (name "Net-(R3-Pad1)") (class "Default")
      (node (ref "R3") (pin "1") (pinfunction "1_1") (pintype "passive"))
      (node (ref "R4") (pin "2") (pinfunction "2_2") (pintype "passive"))
    )
    (net (code "39") (name "Net-(R150-Pad2)") (class "Default")
      (node (ref "R150") (pin "2") (pinfunction "2_2") (pintype "passive"))
      (node (ref "SW2") (pin "1") (pinfunction "1_1") (pintype "passive"))
    )
    (net (code "40") (name "Net-(R152-Pad1)") (class "Default")
      (node (ref "R152") (pin "1") (pinfunction "1_1") (pintype "passive"))
      (node (ref "SW2") (pin "2") (pinfunction "2_2") (pintype "passive"))
    )
    (net (code "41") (name "Net-(R369-Pad1)") (class "Default")
      (node (ref "R369") (pin "1") (pinfunction "1_1") (pintype "passive"))
      (node (ref "R370") (pin "2") (pinfunction "2_2") (pintype "passive"))
    )
    (net (code "42") (name "Net-(U1E-GNDPLL0)") (class "Default")
      (node (ref "C21") (pin "1") (pinfunction "1_1") (pintype "passive"))
      (node (ref "C36") (pin "1") (pinfunction "1_1") (pintype "passive"))
      (node (ref "U1") (pin "N8") (pinfunction "GNDPLL0_N8") (pintype "power_in"))
    )
    (net (code "43") (name "Net-(U1E-GNDPLL1)") (class "Default")
      (node (ref "C31") (pin "1") (pinfunction "1_1") (pintype "passive"))
      (node (ref "C37") (pin "1") (pinfunction "1_1") (pintype "passive"))
      (node (ref "U1") (pin "E7") (pinfunction "GNDPLL1_E7") (pintype "power_in"))
    )
    (net (code "44") (name "Net-(U1E-VPP_FAST)") (class "Default")
      (node (ref "TP1") (pin "1") (pintype "passive"))
      (node (ref "U1") (pin "D12") (pinfunction "VPP_FAST_D12") (pintype "power_in"))
    )
    (net (code "45") (name "P1V2") (class "Default")
      (node (ref "B15") (pin "1") (pinfunction "1_1") (pintype "bidirectional"))
      (node (ref "C22") (pin "2") (pinfunction "2_2") (pintype "passive"))
      (node (ref "C23") (pin "2") (pinfunction "2_2") (pintype "passive"))
      (node (ref "C24") (pin "2") (pinfunction "2_2") (pintype "passive"))
      (node (ref "C25") (pin "2") (pinfunction "2_2") (pintype "passive"))
      (node (ref "C26") (pin "2") (pinfunction "2_2") (pintype "passive"))
      (node (ref "C32") (pin "1") (pinfunction "1_1") (pintype "passive"))
      (node (ref "C38") (pin "2") (pinfunction "2_2") (pintype "passive"))
      (node (ref "C40") (pin "1") (pinfunction "1_1") (pintype "passive"))
      (node (ref "C41") (pin "2") (pinfunction "2_2") (pintype "passive"))
      (node (ref "C89") (pin "2") (pinfunction "2_2") (pintype "passive"))
      (node (ref "L1") (pin "2") (pinfunction "2_2") (pintype "passive"))
      (node (ref "R234") (pin "2") (pinfunction "2_2") (pintype "passive"))
      (node (ref "R92") (pin "1") (pinfunction "1_1") (pintype "passive"))
      (node (ref "R93") (pin "2") (pinfunction "2_2") (pintype "passive"))
      (node (ref "U1") (pin "A14") (pinfunction "VCC_A14") (pintype "power_in"))
      (node (ref "U1") (pin "F10") (pinfunction "VCC_F10") (pintype "power_in"))
      (node (ref "U1") (pin "F6") (pinfunction "VCC_F6") (pintype "power_in"))
      (node (ref "U1") (pin "K10") (pinfunction "VCC_K10") (pintype "power_in"))
      (node (ref "U1") (pin "K6") (pinfunction "VCC_K6") (pintype "power_in"))
      (node (ref "U1") (pin "L2") (pinfunction "VCC_L2") (pintype "power_in"))
    )
    (net (code "46") (name "P2V5") (class "Default")
      (node (ref "B16") (pin "1") (pinfunction "1_1") (pintype "bidirectional"))
      (node (ref "C1") (pin "1") (pinfunction "1_1") (pintype "passive"))
      (node (ref "C11") (pin "2") (pinfunction "2_2") (pintype "passive"))
      (node (ref "C12") (pin "2") (pinfunction "2_2") (pintype "passive"))
      (node (ref "C13") (pin "2") (pinfunction "2_2") (pintype "passive"))
      (node (ref "C14") (pin "2") (pinfunction "2_2") (pintype "passive"))
      (node (ref "C15") (pin "2") (pinfunction "2_2") (pintype "passive"))
      (node (ref "C16") (pin "2") (pinfunction "2_2") (pintype "passive"))
      (node (ref "C17") (pin "2") (pinfunction "2_2") (pintype "passive"))
      (node (ref "C18") (pin "2") (pinfunction "2_2") (pintype "passive"))
      (node (ref "C19") (pin "2") (pinfunction "2_2") (pintype "passive"))
      (node (ref "C20") (pin "2") (pinfunction "2_2") (pintype "passive"))
      (node (ref "C258") (pin "1") (pinfunction "1_1") (pintype "passive"))
      (node (ref "C259") (pin "2") (pinfunction "2_2") (pintype "passive"))
      (node (ref "C27") (pin "2") (pinfunction "2_2") (pintype "passive"))
      (node (ref "C28") (pin "2") (pinfunction "2_2") (pintype "passive"))
      (node (ref "C29") (pin "2") (pinfunction "2_2") (pintype "passive"))
      (node (ref "C30") (pin "2") (pinfunction "2_2") (pintype "passive"))
      (node (ref "C33") (pin "1") (pinfunction "1_1") (pintype "passive"))
      (node (ref "L13") (pin "2") (pinfunction "2_2") (pintype "passive"))
      (node (ref "LD4") (pin "6") (pinfunction "A_6") (pintype "passive"))
      (node (ref "R381") (pin "2") (pinfunction "2_2") (pintype "passive"))
      (node (ref "R62") (pin "1") (pinfunction "1_1") (pintype "passive"))
      (node (ref "U1") (pin "A13") (pinfunction "VCCIO_0_A13") (pintype "power_in"))
      (node (ref "U1") (pin "A3") (pinfunction "VCCIO_0_A3") (pintype "power_in"))
      (node (ref "U1") (pin "A8") (pinfunction "VCCIO_0_A8") (pintype "power_in"))
      (node (ref "U1") (pin "C15") (pinfunction "VCCIO_1_C15") (pintype "power_in"))
      (node (ref "U1") (pin "E1") (pinfunction "VCCIO_3_E1") (pintype "power_in"))
      (node (ref "U1") (pin "E12") (pinfunction "VPP_2V5_E12") (pintype "power_in"))
      (node (ref "U1") (pin "F8") (pinfunction "VCCIO_0_F8") (pintype "power_in"))
      (node (ref "U1") (pin "G6") (pinfunction "VCCIO_3_G6") (pintype "power_in"))
      (node (ref "U1") (pin "H10") (pinfunction "VCCIO_1_H10") (pintype "power_in"))
      (node (ref "U1") (pin "H15") (pinfunction "VCCIO_1_H15") (pintype "power_in"))
      (node (ref "U1") (pin "J6") (pinfunction "VCCIO_3_J6") (pintype "power_in"))
      (node (ref "U1") (pin "K8") (pinfunction "VCCIO_2_K8") (pintype "power_in"))
      (node (ref "U1") (pin "N1") (pinfunction "VCCIO_3_N1") (pintype "power_in"))
      (node (ref "U1") (pin "N13") (pinfunction "VCC_SPI_N13") (pintype "power_in"))
      (node (ref "U1") (pin "N15") (pinfunction "VCCIO_1_N15") (pintype "power_in"))
      (node (ref "U1") (pin "P3") (pinfunction "VCCIO_2_P3") (pintype "power_in"))
      (node (ref "U1") (pin "R13") (pinfunction "VCCIO_2_R13") (pintype "power_in"))
      (node (ref "U1") (pin "R8") (pinfunction "VCCIO_2_R8") (pintype "power_in"))
    )
    (net (code "47") (name "P3V3MP") (class "Default")
      (node (ref "B7") (pin "1") (pinfunction "1_1") (pintype "bidirectional"))
      (node (ref "C34") (pin "2") (pinfunction "2_2") (pintype "passive"))
      (node (ref "C35") (pin "2") (pinfunction "2_2") (pintype "passive"))
      (node (ref "IC2") (pin "8") (pinfunction "+VS_8") (pintype "power_in"))
      (node (ref "IC3") (pin "8") (pinfunction "+VS_8") (pintype "power_in"))
      (node (ref "JP2") (pin "2") (pinfunction "E2_2") (pintype "passive"))
      (node (ref "R164") (pin "1") (pinfunction "1_1") (pintype "passive"))
      (node (ref "R166") (pin "1") (pinfunction "1_1") (pintype "passive"))
      (node (ref "R2") (pin "2") (pinfunction "2_2") (pintype "passive"))
      (node (ref "R44") (pin "2") (pinfunction "2_2") (pintype "passive"))
    )
    (net (code "48") (name "P5V0") (class "Default")
      (node (ref "B5") (pin "1") (pinfunction "1_1") (pintype "bidirectional"))
      (node (ref "C244") (pin "2") (pinfunction "2_2") (pintype "passive"))
      (node (ref "C245") (pin "2") (pinfunction "2_2") (pintype "passive"))
      (node (ref "C246") (pin "2") (pinfunction "2_2") (pintype "passive"))
      (node (ref "C247") (pin "2") (pinfunction "2_2") (pintype "passive"))
      (node (ref "C252") (pin "2") (pinfunction "2_2") (pintype "passive"))
      (node (ref "C257") (pin "2") (pinfunction "2_2") (pintype "passive"))
      (node (ref "C39") (pin "2") (pinfunction "2_2") (pintype "passive"))
      (node (ref "C42") (pin "2") (pinfunction "2_2") (pintype "passive"))
      (node (ref "IC4") (pin "2") (pinfunction "EN_2") (pintype "input"))
      (node (ref "IC4") (pin "3") (pinfunction "VIN_3") (pintype "input"))
      (node (ref "IC5") (pin "1") (pinfunction "VIN_1") (pintype "input"))
      (node (ref "IC5") (pin "3") (pinfunction "EN_3") (pintype "input"))
      (node (ref "IC87") (pin "12") (pinfunction "VOUT_12") (pintype "power_in"))
      (node (ref "IC87") (pin "13") (pinfunction "VOUT_13") (pintype "power_in"))
      (node (ref "IC87") (pin "14") (pinfunction "VOUT_14") (pintype "power_in"))
      (node (ref "IC87") (pin "15") (pinfunction "VOUT_15") (pintype "power_in"))
      (node (ref "IC87") (pin "16") (pinfunction "VOUT_16") (pintype "power_in"))
      (node (ref "IC87") (pin "17") (pinfunction "VOUT_17") (pintype "power_in"))
      (node (ref "IC87") (pin "18") (pinfunction "VOUT_18") (pintype "power_in"))
      (node (ref "IC87") (pin "19") (pinfunction "VOUT_19") (pintype "power_in"))
      (node (ref "IC87") (pin "20") (pinfunction "VOUT_20") (pintype "power_in"))
      (node (ref "IC87") (pin "21") (pinfunction "VOUT_21") (pintype "power_in"))
      (node (ref "IC90") (pin "2") (pinfunction "EN_2") (pintype "input"))
      (node (ref "IC90") (pin "3") (pinfunction "VIN_3") (pintype "input"))
      (node (ref "R3") (pin "2") (pinfunction "2_2") (pintype "passive"))
      (node (ref "R367") (pin "2") (pinfunction "2_2") (pintype "passive"))
    )
    (net (code "49") (name "P12V0") (class "Default")
      (node (ref "B8") (pin "1") (pinfunction "1_1") (pintype "bidirectional"))
      (node (ref "C249") (pin "2") (pinfunction "2_2") (pintype "passive"))
      (node (ref "C250") (pin "2") (pinfunction "2_2") (pintype "passive"))
      (node (ref "C251") (pin "2") (pinfunction "2_2") (pintype "passive"))
      (node (ref "C84") (pin "1") (pinfunction "1_1") (pintype "passive"))
      (node (ref "FL1") (pin "2") (pinfunction "CB_2") (pintype "passive"))
      (node (ref "IC87") (pin "1") (pinfunction "PVIN_1") (pintype "power_in"))
      (node (ref "IC87") (pin "2") (pinfunction "PVIN_2") (pintype "power_in"))
      (node (ref "IC87") (pin "39") (pinfunction "VIN_39") (pintype "power_in"))
      (node (ref "IC87") (pin "52") (pinfunction "PVIN_52") (pintype "power_in"))
      (node (ref "R98") (pin "2") (pinfunction "2_2") (pintype "passive"))
    )
    (net (code "50") (name "P12V0F") (class "Default")
      (node (ref "FL1") (pin "1") (pinfunction "B_1") (pintype "passive"))
      (node (ref "J6") (pin "3") (pinfunction "3_3") (pintype "bidirectional"))
      (node (ref "J8") (pin "3") (pinfunction "3_3") (pintype "bidirectional"))
      (node (ref "J8") (pin "4") (pinfunction "4_4") (pintype "bidirectional"))
    )
    (net (code "51") (name "unconnected-(IC4-NC-Pad1)") (class "Default")
      (node (ref "IC4") (pin "1") (pinfunction "NC_1") (pintype "passive"))
    )
    (net (code "52") (name "unconnected-(IC5-NC-Pad4)") (class "Default")
      (node (ref "IC5") (pin "4") (pinfunction "NC_4") (pintype "passive"))
    )
    (net (code "53") (name "unconnected-(IC87-NC-Pad23)") (class "Default")
      (node (ref "IC87") (pin "23") (pinfunction "NC_23") (pintype "passive+no_connect"))
    )
    (net (code "54") (name "unconnected-(IC87-NC-Pad24)") (class "Default")
      (node (ref "IC87") (pin "24") (pinfunction "NC_24") (pintype "passive+no_connect"))
    )
    (net (code "55") (name "unconnected-(IC87-NC-Pad25)") (class "Default")
      (node (ref "IC87") (pin "25") (pinfunction "NC_25") (pintype "passive+no_connect"))
    )
    (net (code "56") (name "unconnected-(IC87-NC-Pad27)") (class "Default")
      (node (ref "IC87") (pin "27") (pinfunction "NC_27") (pintype "passive+no_connect"))
    )
    (net (code "57") (name "unconnected-(IC87-NC-Pad28)") (class "Default")
      (node (ref "IC87") (pin "28") (pinfunction "NC_28") (pintype "passive+no_connect"))
    )
    (net (code "58") (name "unconnected-(IC87-NC-Pad29)") (class "Default")
      (node (ref "IC87") (pin "29") (pinfunction "NC_29") (pintype "passive+no_connect"))
    )
    (net (code "59") (name "unconnected-(IC87-NC-Pad30)") (class "Default")
      (node (ref "IC87") (pin "30") (pinfunction "NC_30") (pintype "passive+no_connect"))
    )
    (net (code "60") (name "unconnected-(IC87-NC-Pad32)") (class "Default")
      (node (ref "IC87") (pin "32") (pinfunction "NC_32") (pintype "passive+no_connect"))
    )
    (net (code "61") (name "unconnected-(IC87-NC-Pad33)") (class "Default")
      (node (ref "IC87") (pin "33") (pinfunction "NC_33") (pintype "passive+no_connect"))
    )
    (net (code "62") (name "unconnected-(IC87-NC-Pad34)") (class "Default")
      (node (ref "IC87") (pin "34") (pinfunction "NC_34") (pintype "passive+no_connect"))
    )
    (net (code "63") (name "unconnected-(IC87-NC-Pad40)") (class "Default")
      (node (ref "IC87") (pin "40") (pinfunction "NC_40") (pintype "passive+no_connect"))
    )
    (net (code "64") (name "unconnected-(IC87-NC-Pad41)") (class "Default")
      (node (ref "IC87") (pin "41") (pinfunction "NC_41") (pintype "passive+no_connect"))
    )
    (net (code "65") (name "unconnected-(IC90-NC-Pad1)") (class "Default")
      (node (ref "IC90") (pin "1") (pinfunction "NC_1") (pintype "passive"))
    )
    (net (code "66") (name "unconnected-(J6-Pad2)") (class "Default")
      (node (ref "J6") (pin "2") (pinfunction "2_2") (pintype "bidirectional"))
    )
  )
)
